# LED.net
KiCad netlist of a schematic drawn in Altium Designer
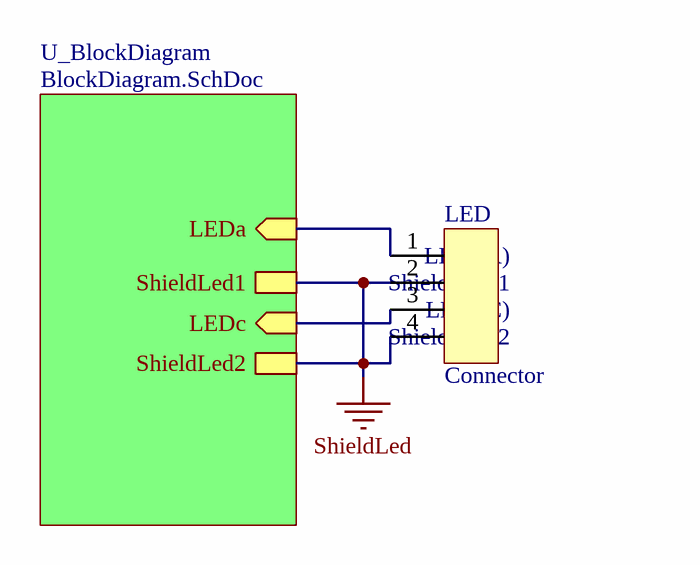
[diagram p0: LED.SchDoc]

(export (version "E")
  (design (tool "Eeschema 10.0.6"))
  (components
    (comp (ref "LED")
      (value "LED")
      (footprint "MicroMatch4p")
      (fields (field (name "SYSTEM") "Connector"))
      (libsource (lib "Balance") (part "MicroMatch4p"))
    )
  )
  (nets
    (net (code "1") (name "/LEDa") (class "Default") (node (ref "LED") (pin "1") (pintype "passive")))
    (net (code "2") (name "/LEDc") (class "Default") (node (ref "LED") (pin "3") (pintype "passive")))
    (net (code "3") (name "ShieldLed") (class "Default")
      (node (ref "LED") (pin "2") (pintype "passive"))
      (node (ref "LED") (pin "4") (pintype "passive"))
    )
  )
)
